# sensnodeTXv3.net
KiCad netlist of a schematic drawn in EAGLE
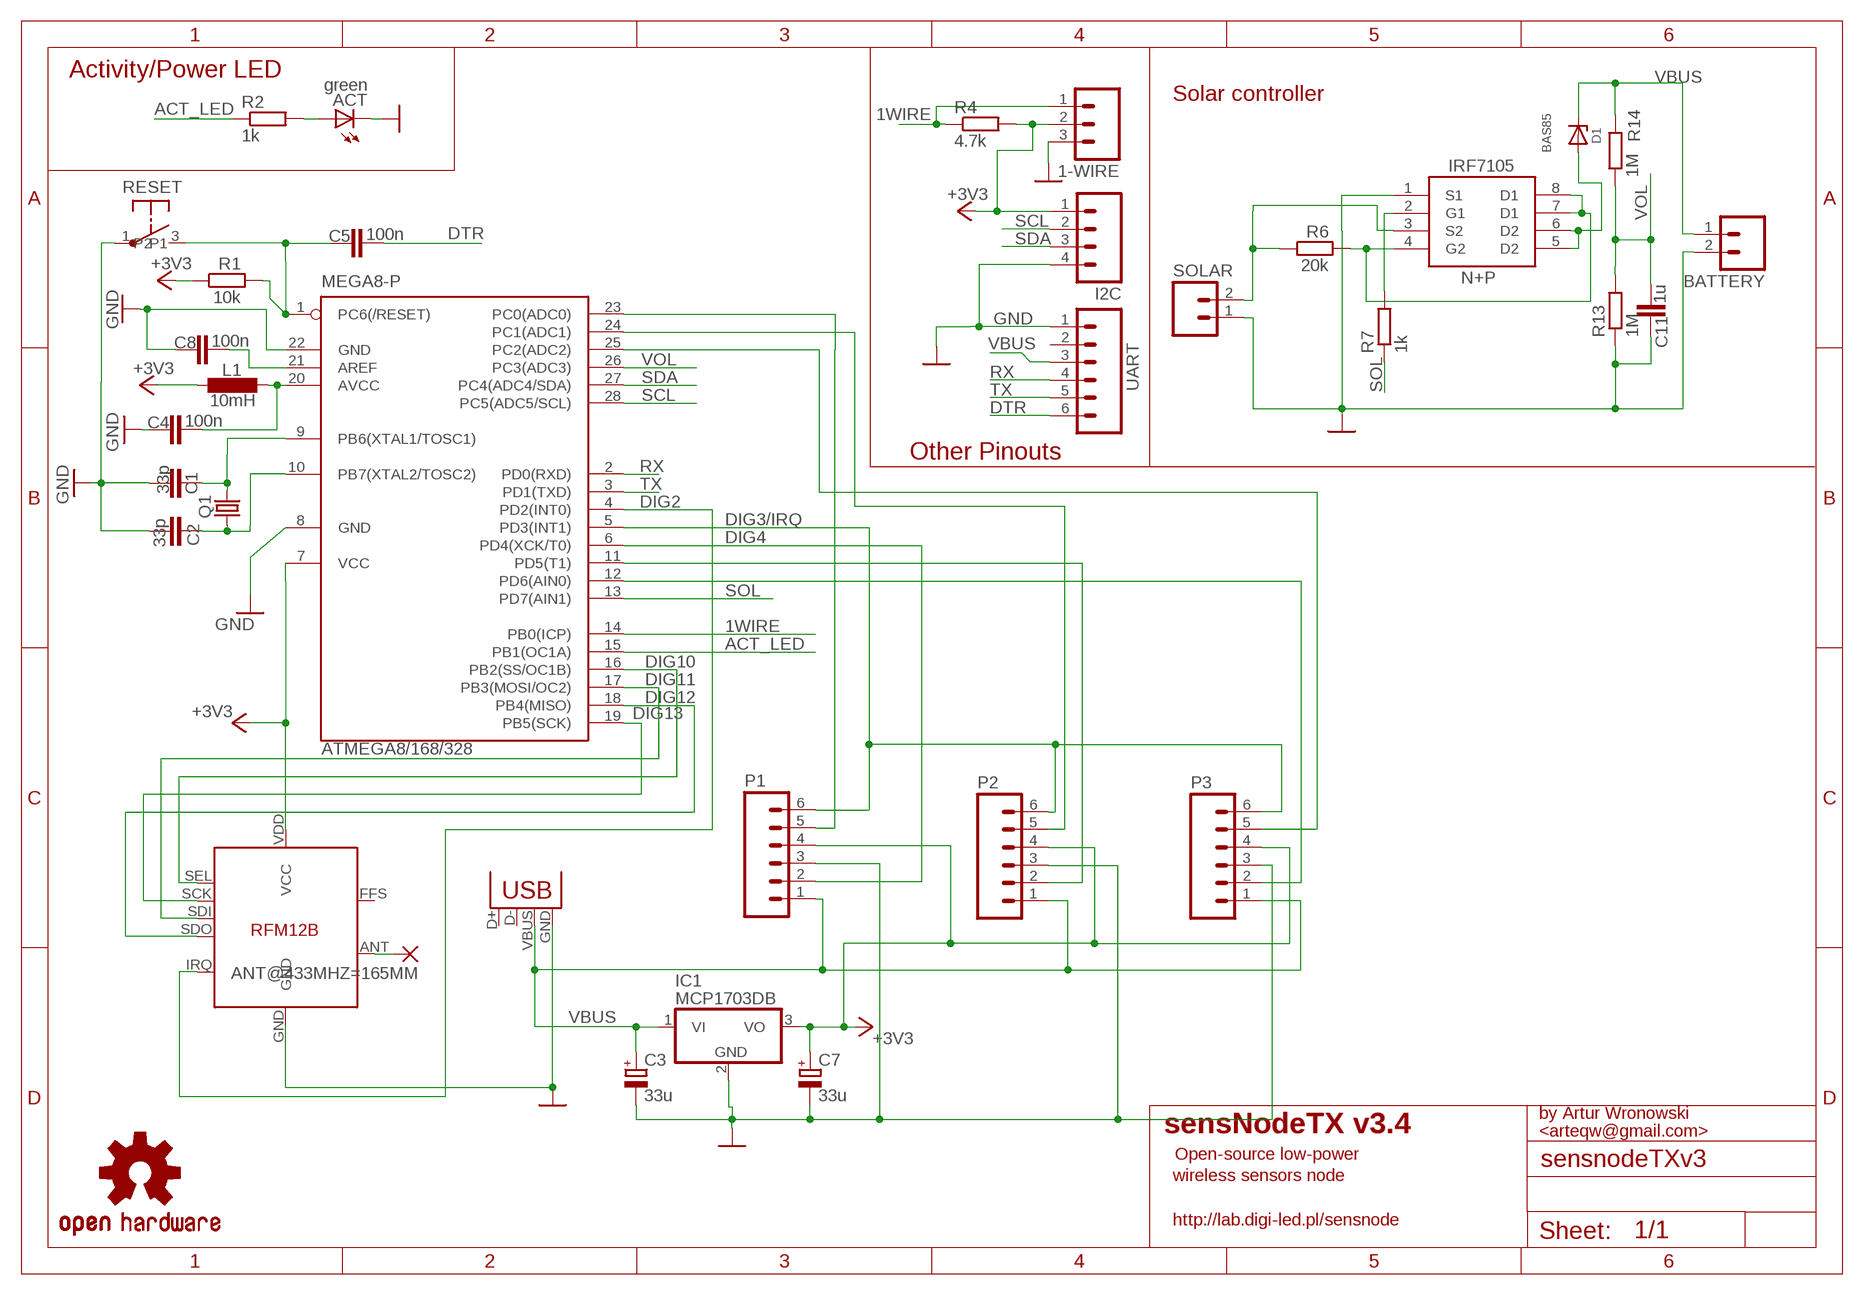
[diagram p0: schematic, sheet 1]

(export (version "E")
  (design (tool "Eeschema 10.0.6"))
  (components
    (comp (ref "1-WIRE")
      (value "M03LOCK")
      (footprint "eagle-import:1X03_LOCK")
      (libsource (lib "eagle-import") (part "M03LOCK"))
    )
    (comp (ref "ACT")
      (value "green")
      (footprint "eagle-import:1206")
      (libsource (lib "eagle-import") (part "LEDSMT1206"))
    )
    (comp (ref "ANT@433MHZ=165MM")
      (value "2,15/1,0")
      (footprint "eagle-import:2,15_1,0")
      (libsource (lib "eagle-import") (part "2,15/1,0"))
    )
    (comp (ref "ATMEGA8/168/328")
      (value "MEGA8-P")
      (footprint "eagle-import:DIL28-3")
      (libsource (lib "eagle-import") (part "MEGA8-P"))
    )
    (comp (ref "BATTERY")
      (value "M02LOCK")
      (footprint "eagle-import:1X02_LOCK")
      (libsource (lib "eagle-import") (part "M02LOCK"))
    )
    (comp (ref "C1")
      (value "33p")
      (footprint "eagle-import:C0805")
      (libsource (lib "eagle-import") (part "C-EUC0805"))
    )
    (comp (ref "C2")
      (value "33p")
      (footprint "eagle-import:C0805")
      (libsource (lib "eagle-import") (part "C-EUC0805"))
    )
    (comp (ref "C3")
      (value "33u")
      (footprint "eagle-import:SMC_B")
      (libsource (lib "eagle-import") (part "CPOL-EUSMCB"))
    )
    (comp (ref "C4")
      (value "100n")
      (footprint "eagle-import:C0805")
      (libsource (lib "eagle-import") (part "C-EUC0805"))
    )
    (comp (ref "C5")
      (value "100n")
      (footprint "eagle-import:C0805")
      (libsource (lib "eagle-import") (part "C-EUC0805"))
    )
    (comp (ref "C7")
      (value "33u")
      (footprint "eagle-import:SMC_B")
      (libsource (lib "eagle-import") (part "CPOL-EUSMCB"))
    )
    (comp (ref "C8")
      (value "100n")
      (footprint "eagle-import:C0805")
      (libsource (lib "eagle-import") (part "C-EUC0805"))
    )
    (comp (ref "C11")
      (value "1u")
      (footprint "eagle-import:C0805")
      (libsource (lib "eagle-import") (part "C-EUC0805"))
    )
    (comp (ref "D1")
      (value "BAS85")
      (footprint "eagle-import:SOD80C")
      (libsource (lib "eagle-import") (part "ZENER-DIODESOD80C"))
    )
    (comp (ref "I2C")
      (value "M04LOCK")
      (footprint "eagle-import:1X04_LOCK")
      (libsource (lib "eagle-import") (part "M04LOCK"))
    )
    (comp (ref "IC1")
      (value "MCP1703DB")
      (footprint "eagle-import:SOT223")
      (libsource (lib "eagle-import") (part "MCP1703DB"))
    )
    (comp (ref "L1")
      (value "10mH")
      (footprint "eagle-import:0207_7")
      (libsource (lib "eagle-import") (part "L-EU0207/7"))
    )
    (comp (ref "P1")
      (value "M06SIP_LOCK")
      (footprint "eagle-import:1X06-SIP_LOCK")
      (libsource (lib "eagle-import") (part "M06SIP_LOCK"))
    )
    (comp (ref "P2")
      (value "M06SIP_LOCK")
      (footprint "eagle-import:1X06-SIP_LOCK")
      (libsource (lib "eagle-import") (part "M06SIP_LOCK"))
    )
    (comp (ref "P3")
      (value "M06SIP_LOCK")
      (footprint "eagle-import:1X06-SIP_LOCK")
      (libsource (lib "eagle-import") (part "M06SIP_LOCK"))
    )
    (comp (ref "Q1")
      (value "CRYSTALHC49U70")
      (footprint "eagle-import:HC49U70")
      (libsource (lib "eagle-import") (part "CRYSTALHC49U70"))
    )
    (comp (ref "R1")
      (value "10k")
      (footprint "eagle-import:M0805")
      (libsource (lib "eagle-import") (part "R-EU_M0805"))
    )
    (comp (ref "R2")
      (value "1k")
      (footprint "eagle-import:M0805")
      (libsource (lib "eagle-import") (part "R-EU_M0805"))
    )
    (comp (ref "R4")
      (value "4.7k")
      (footprint "eagle-import:M0805")
      (libsource (lib "eagle-import") (part "R-EU_M0805"))
    )
    (comp (ref "R6")
      (value "20k")
      (footprint "eagle-import:M0805")
      (libsource (lib "eagle-import") (part "R-EU_M0805"))
    )
    (comp (ref "R7")
      (value "1k")
      (footprint "eagle-import:M0805")
      (libsource (lib "eagle-import") (part "R-EU_M0805"))
    )
    (comp (ref "R13")
      (value "1M")
      (footprint "eagle-import:M0805")
      (libsource (lib "eagle-import") (part "R-EU_M0805"))
    )
    (comp (ref "R14")
      (value "1M")
      (footprint "eagle-import:M0805")
      (libsource (lib "eagle-import") (part "R-EU_M0805"))
    )
    (comp (ref "RESET")
      (value "TACT3X6")
      (footprint "eagle-import:TACK3X6")
      (libsource (lib "eagle-import") (part "TACT3X6"))
    )
    (comp (ref "RFM12B")
      (value "RFM12B")
      (footprint "eagle-import:RFM12B")
      (libsource (lib "eagle-import") (part "RFM12B"))
    )
    (comp (ref "SOLAR")
      (value "M02LOCK")
      (footprint "eagle-import:1X02_LOCK")
      (libsource (lib "eagle-import") (part "M02LOCK"))
    )
    (comp (ref "U$3")
      (value "OSHW-LOGOM")
      (footprint "eagle-import:OSHW-LOGO-M")
      (libsource (lib "eagle-import") (part "OSHW-LOGOM"))
    )
    (comp (ref "U$4")
      (value "IRF7105")
      (footprint "eagle-import:SO8")
      (libsource (lib "eagle-import") (part "IRF7104"))
    )
    (comp (ref "UART")
      (value "M06SIP_LOCK")
      (footprint "eagle-import:1X06-SIP_LOCK")
      (libsource (lib "eagle-import") (part "M06SIP_LOCK"))
    )
    (comp (ref "USB_PWR")
      (value "USBSMD")
      (footprint "eagle-import:USB-MINIB")
      (libsource (lib "eagle-import") (part "USBSMD"))
    )
  )
  (nets
    (net (code "1") (name "+3V3") (class "Default")
      (node (ref "1-WIRE") (pin "2") (pinfunction "2_2") (pintype "passive"))
      (node (ref "ATMEGA8/168/328") (pin "7") (pinfunction "VCC_7") (pintype "power_in"))
      (node (ref "C7") (pin "+") (pinfunction "+_+") (pintype "passive"))
      (node (ref "I2C") (pin "1") (pinfunction "1_1") (pintype "passive"))
      (node (ref "IC1") (pin "3") (pinfunction "VO_3") (pintype "passive"))
      (node (ref "L1") (pin "1") (pinfunction "1_1") (pintype "passive"))
      (node (ref "P1") (pin "4") (pinfunction "4_4") (pintype "passive"))
      (node (ref "P2") (pin "4") (pinfunction "4_4") (pintype "passive"))
      (node (ref "P3") (pin "4") (pinfunction "4_4") (pintype "passive"))
      (node (ref "R1") (pin "1") (pinfunction "1_1") (pintype "passive"))
      (node (ref "R4") (pin "2") (pinfunction "2_2") (pintype "passive"))
      (node (ref "RFM12B") (pin "VDD") (pinfunction "VCC_VDD") (pintype "power_in"))
    )
    (net (code "2") (name "/1WIRE") (class "Default")
      (node (ref "1-WIRE") (pin "1") (pinfunction "1_1") (pintype "passive"))
      (node (ref "ATMEGA8/168/328") (pin "14") (pinfunction "PB0(ICP)_14") (pintype "bidirectional"))
      (node (ref "R4") (pin "1") (pinfunction "1_1") (pintype "passive"))
    )
    (net (code "3") (name "/ACT_LED") (class "Default")
      (node (ref "ATMEGA8/168/328") (pin "15") (pinfunction "PB1(OC1A)_15") (pintype "bidirectional"))
      (node (ref "R2") (pin "1") (pinfunction "1_1") (pintype "passive"))
    )
    (net (code "4") (name "/DIG2") (class "Default")
      (node (ref "ATMEGA8/168/328") (pin "4") (pinfunction "PD2(INT0)_4") (pintype "bidirectional"))
      (node (ref "RFM12B") (pin "IRQ") (pinfunction "IRQ_IRQ") (pintype "open_collector"))
    )
    (net (code "5") (name "/DIG3{slash}IRQ") (class "Default")
      (node (ref "ATMEGA8/168/328") (pin "5") (pinfunction "PD3(INT1)_5") (pintype "bidirectional"))
      (node (ref "P1") (pin "6") (pinfunction "6_6") (pintype "passive"))
      (node (ref "P2") (pin "6") (pinfunction "6_6") (pintype "passive"))
      (node (ref "P3") (pin "6") (pinfunction "6_6") (pintype "passive"))
    )
    (net (code "6") (name "/DIG4") (class "Default")
      (node (ref "ATMEGA8/168/328") (pin "6") (pinfunction "PD4(XCK/T0)_6") (pintype "bidirectional"))
      (node (ref "P1") (pin "2") (pinfunction "2_2") (pintype "passive"))
    )
    (net (code "7") (name "/DIG10") (class "Default")
      (node (ref "ATMEGA8/168/328") (pin "16") (pinfunction "PB2(SS/OC1B)_16") (pintype "bidirectional"))
      (node (ref "RFM12B") (pin "SEL") (pinfunction "SEL_SEL") (pintype "input"))
    )
    (net (code "8") (name "/DIG11") (class "Default")
      (node (ref "ATMEGA8/168/328") (pin "17") (pinfunction "PB3(MOSI/OC2)_17") (pintype "bidirectional"))
      (node (ref "RFM12B") (pin "SDI") (pinfunction "SDI_SDI") (pintype "input"))
    )
    (net (code "9") (name "/DIG12") (class "Default")
      (node (ref "ATMEGA8/168/328") (pin "18") (pinfunction "PB4(MISO)_18") (pintype "bidirectional"))
      (node (ref "RFM12B") (pin "SDO") (pinfunction "SDO_SDO") (pintype "output"))
    )
    (net (code "10") (name "/DIG13") (class "Default")
      (node (ref "ATMEGA8/168/328") (pin "19") (pinfunction "PB5(SCK)_19") (pintype "bidirectional"))
      (node (ref "RFM12B") (pin "SCK") (pinfunction "SCK_SCK") (pintype "input"))
    )
    (net (code "11") (name "/DTR") (class "Default")
      (node (ref "C5") (pin "1") (pinfunction "1_1") (pintype "passive"))
      (node (ref "UART") (pin "6") (pinfunction "6_6") (pintype "passive"))
    )
    (net (code "12") (name "/RX") (class "Default")
      (node (ref "ATMEGA8/168/328") (pin "2") (pinfunction "PD0(RXD)_2") (pintype "bidirectional"))
      (node (ref "UART") (pin "4") (pinfunction "4_4") (pintype "passive"))
    )
    (net (code "13") (name "/SCL") (class "Default")
      (node (ref "ATMEGA8/168/328") (pin "28") (pinfunction "PC5(ADC5/SCL)_28") (pintype "bidirectional"))
      (node (ref "I2C") (pin "2") (pinfunction "2_2") (pintype "passive"))
    )
    (net (code "14") (name "/SDA") (class "Default")
      (node (ref "ATMEGA8/168/328") (pin "27") (pinfunction "PC4(ADC4/SDA)_27") (pintype "bidirectional"))
      (node (ref "I2C") (pin "3") (pinfunction "3_3") (pintype "passive"))
    )
    (net (code "15") (name "/SOL") (class "Default")
      (node (ref "ATMEGA8/168/328") (pin "13") (pinfunction "PD7(AIN1)_13") (pintype "bidirectional"))
      (node (ref "R7") (pin "1") (pinfunction "1_1") (pintype "passive"))
    )
    (net (code "16") (name "/TX") (class "Default")
      (node (ref "ATMEGA8/168/328") (pin "3") (pinfunction "PD1(TXD)_3") (pintype "bidirectional"))
      (node (ref "UART") (pin "5") (pinfunction "5_5") (pintype "passive"))
    )
    (net (code "17") (name "/VBUS") (class "Default")
      (node (ref "BATTERY") (pin "1") (pinfunction "1_1") (pintype "passive"))
      (node (ref "C3") (pin "+") (pinfunction "+_+") (pintype "passive"))
      (node (ref "D1") (pin "C") (pinfunction "C_C") (pintype "passive"))
      (node (ref "IC1") (pin "1") (pinfunction "VI_1") (pintype "input"))
      (node (ref "P1") (pin "1") (pinfunction "1_1") (pintype "passive"))
      (node (ref "P2") (pin "1") (pinfunction "1_1") (pintype "passive"))
      (node (ref "P3") (pin "1") (pinfunction "1_1") (pintype "passive"))
      (node (ref "R14") (pin "2") (pinfunction "2_2") (pintype "passive"))
      (node (ref "UART") (pin "3") (pinfunction "3_3") (pintype "passive"))
      (node (ref "USB_PWR") (pin "VBUS") (pinfunction "VBUS_VBUS") (pintype "bidirectional"))
    )
    (net (code "18") (name "/VOL") (class "Default")
      (node (ref "ATMEGA8/168/328") (pin "26") (pinfunction "PC3(ADC3)_26") (pintype "bidirectional"))
      (node (ref "C11") (pin "1") (pinfunction "1_1") (pintype "passive"))
      (node (ref "R13") (pin "2") (pinfunction "2_2") (pintype "passive"))
      (node (ref "R14") (pin "1") (pinfunction "1_1") (pintype "passive"))
    )
    (net (code "19") (name "GND") (class "Default")
      (node (ref "1-WIRE") (pin "3") (pinfunction "3_3") (pintype "passive"))
      (node (ref "ACT") (pin "C") (pinfunction "C_C") (pintype "passive"))
      (node (ref "ATMEGA8/168/328") (pin "22") (pinfunction "GND_22") (pintype "power_in"))
      (node (ref "ATMEGA8/168/328") (pin "8") (pinfunction "GND_8") (pintype "power_in"))
      (node (ref "BATTERY") (pin "2") (pinfunction "2_2") (pintype "passive"))
      (node (ref "C1") (pin "2") (pinfunction "2_2") (pintype "passive"))
      (node (ref "C11") (pin "2") (pinfunction "2_2") (pintype "passive"))
      (node (ref "C2") (pin "2") (pinfunction "2_2") (pintype "passive"))
      (node (ref "C3") (pin "-") (pinfunction "-_-") (pintype "passive"))
      (node (ref "C4") (pin "2") (pinfunction "2_2") (pintype "passive"))
      (node (ref "C7") (pin "-") (pinfunction "-_-") (pintype "passive"))
      (node (ref "C8") (pin "2") (pinfunction "2_2") (pintype "passive"))
      (node (ref "I2C") (pin "4") (pinfunction "4_4") (pintype "passive"))
      (node (ref "IC1") (pin "2") (pinfunction "GND_2") (pintype "passive"))
      (node (ref "P1") (pin "3") (pinfunction "3_3") (pintype "passive"))
      (node (ref "P2") (pin "3") (pinfunction "3_3") (pintype "passive"))
      (node (ref "P3") (pin "3") (pinfunction "3_3") (pintype "passive"))
      (node (ref "R13") (pin "1") (pinfunction "1_1") (pintype "passive"))
      (node (ref "RESET") (pin "1") (pinfunction "P1_1") (pintype "power_in"))
      (node (ref "RFM12B") (pin "GND") (pinfunction "GND_GND") (pintype "power_in"))
      (node (ref "SOLAR") (pin "1") (pinfunction "1_1") (pintype "passive"))
      (node (ref "U$4") (pin "1") (pinfunction "S1_1") (pintype "bidirectional"))
      (node (ref "UART") (pin "1") (pinfunction "1_1") (pintype "passive"))
      (node (ref "USB_PWR") (pin "GND") (pinfunction "GND_GND") (pintype "bidirectional"))
    )
    (net (code "20") (name "Net-(ACT-PadA)") (class "Default")
      (node (ref "ACT") (pin "A") (pinfunction "A_A") (pintype "passive"))
      (node (ref "R2") (pin "2") (pinfunction "2_2") (pintype "passive"))
    )
    (net (code "21") (name "Net-(ANT@433MHZ=165MM-P)") (class "Default")
      (node (ref "ANT@433MHZ=165MM") (pin "1") (pinfunction "P_1") (pintype "passive"))
      (node (ref "RFM12B") (pin "ANT") (pinfunction "ANT_ANT") (pintype "passive"))
    )
    (net (code "22") (name "Net-(ATMEGA8/168/328-AREF)") (class "Default")
      (node (ref "ATMEGA8/168/328") (pin "21") (pinfunction "AREF_21") (pintype "passive"))
      (node (ref "C8") (pin "1") (pinfunction "1_1") (pintype "passive"))
    )
    (net (code "23") (name "Net-(ATMEGA8/168/328-AVCC)") (class "Default")
      (node (ref "ATMEGA8/168/328") (pin "20") (pinfunction "AVCC_20") (pintype "power_in"))
      (node (ref "C4") (pin "1") (pinfunction "1_1") (pintype "passive"))
      (node (ref "L1") (pin "2") (pinfunction "2_2") (pintype "passive"))
    )
    (net (code "24") (name "Net-(ATMEGA8/168/328-PB6(XTAL1{slash}TOSC1))") (class "Default")
      (node (ref "ATMEGA8/168/328") (pin "9") (pinfunction "PB6(XTAL1/TOSC1)_9") (pintype "bidirectional"))
      (node (ref "C1") (pin "1") (pinfunction "1_1") (pintype "passive"))
      (node (ref "Q1") (pin "2") (pinfunction "2_2") (pintype "passive"))
    )
    (net (code "25") (name "Net-(ATMEGA8/168/328-PB7(XTAL2{slash}TOSC2))") (class "Default")
      (node (ref "ATMEGA8/168/328") (pin "10") (pinfunction "PB7(XTAL2/TOSC2)_10") (pintype "bidirectional"))
      (node (ref "C2") (pin "1") (pinfunction "1_1") (pintype "passive"))
      (node (ref "Q1") (pin "1") (pinfunction "1_1") (pintype "passive"))
    )
    (net (code "26") (name "Net-(ATMEGA8/168/328-PC0(ADC0))") (class "Default")
      (node (ref "ATMEGA8/168/328") (pin "23") (pinfunction "PC0(ADC0)_23") (pintype "bidirectional"))
      (node (ref "P1") (pin "5") (pinfunction "5_5") (pintype "passive"))
    )
    (net (code "27") (name "Net-(ATMEGA8/168/328-PC1(ADC1))") (class "Default")
      (node (ref "ATMEGA8/168/328") (pin "24") (pinfunction "PC1(ADC1)_24") (pintype "bidirectional"))
      (node (ref "P2") (pin "5") (pinfunction "5_5") (pintype "passive"))
    )
    (net (code "28") (name "Net-(ATMEGA8/168/328-PC2(ADC2))") (class "Default")
      (node (ref "ATMEGA8/168/328") (pin "25") (pinfunction "PC2(ADC2)_25") (pintype "bidirectional"))
      (node (ref "P3") (pin "5") (pinfunction "5_5") (pintype "passive"))
    )
    (net (code "29") (name "Net-(ATMEGA8/168/328-PC6({slash}RESET))") (class "Default")
      (node (ref "ATMEGA8/168/328") (pin "1") (pinfunction "PC6(/RESET)_1") (pintype "bidirectional"))
      (node (ref "C5") (pin "2") (pinfunction "2_2") (pintype "passive"))
      (node (ref "R1") (pin "2") (pinfunction "2_2") (pintype "passive"))
      (node (ref "RESET") (pin "3") (pinfunction "P2_3") (pintype "power_in"))
    )
    (net (code "30") (name "Net-(ATMEGA8/168/328-PD5(T1))") (class "Default")
      (node (ref "ATMEGA8/168/328") (pin "11") (pinfunction "PD5(T1)_11") (pintype "bidirectional"))
      (node (ref "P2") (pin "2") (pinfunction "2_2") (pintype "passive"))
    )
    (net (code "31") (name "Net-(ATMEGA8/168/328-PD6(AIN0))") (class "Default")
      (node (ref "ATMEGA8/168/328") (pin "12") (pinfunction "PD6(AIN0)_12") (pintype "bidirectional"))
      (node (ref "P3") (pin "2") (pinfunction "2_2") (pintype "passive"))
    )
    (net (code "32") (name "Net-(D1-PadA)") (class "Default")
      (node (ref "D1") (pin "A") (pinfunction "A_A") (pintype "passive"))
      (node (ref "U$4") (pin "5") (pinfunction "D2_5") (pintype "bidirectional"))
      (node (ref "U$4") (pin "6") (pinfunction "D2_6") (pintype "bidirectional"))
    )
    (net (code "33") (name "Net-(U$4-G1)") (class "Default")
      (node (ref "R7") (pin "2") (pinfunction "2_2") (pintype "passive"))
      (node (ref "U$4") (pin "2") (pinfunction "G1_2") (pintype "bidirectional"))
    )
    (net (code "34") (name "Net-(U$4-G2)") (class "Default")
      (node (ref "R6") (pin "2") (pinfunction "2_2") (pintype "passive"))
      (node (ref "U$4") (pin "4") (pinfunction "G2_4") (pintype "bidirectional"))
      (node (ref "U$4") (pin "7") (pinfunction "D1_7") (pintype "bidirectional"))
      (node (ref "U$4") (pin "8") (pinfunction "D1_8") (pintype "bidirectional"))
    )
    (net (code "35") (name "Net-(U$4-S2)") (class "Default")
      (node (ref "R6") (pin "1") (pinfunction "1_1") (pintype "passive"))
      (node (ref "SOLAR") (pin "2") (pinfunction "2_2") (pintype "passive"))
      (node (ref "U$4") (pin "3") (pinfunction "S2_3") (pintype "bidirectional"))
    )
    (net (code "36") (name "unconnected-(RFM12B-PadFFS)") (class "Default")
      (node (ref "RFM12B") (pin "FFS") (pinfunction "FFS_FFS") (pintype "bidirectional"))
    )
    (net (code "37") (name "unconnected-(UART-Pad2)") (class "Default")
      (node (ref "UART") (pin "2") (pinfunction "2_2") (pintype "passive"))
    )
    (net (code "38") (name "unconnected-(USB_PWR-PadD+)") (class "Default")
      (node (ref "USB_PWR") (pin "D+") (pinfunction "D+_D+") (pintype "bidirectional"))
    )
    (net (code "39") (name "unconnected-(USB_PWR-PadD-)") (class "Default")
      (node (ref "USB_PWR") (pin "D-") (pinfunction "D-_D-") (pintype "bidirectional"))
    )
  )
)
